# 74LV2G07DBVR.net
KiCad netlist of a schematic drawn in EAGLE
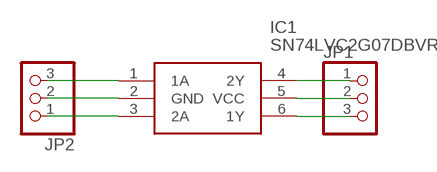
[diagram p0: schematic, sheet 1]

(export (version "E")
  (design (tool "Eeschema 10.0.6"))
  (components
    (comp (ref "IC1")
      (value "SN74LVC2G07DBVR")
      (footprint "eagle-import:SOT95P280X145-6N")
      (fields (field (name "RS_PART_NUMBER") "6628913P"))
      (libsource (lib "eagle-import") (part "SN74LVC2G07DBVR"))
    )
    (comp (ref "JP1")
      (value "PINHD-1X3")
      (footprint "eagle-import:1X03")
      (libsource (lib "eagle-import") (part "PINHD-1X3"))
    )
    (comp (ref "JP2")
      (value "PINHD-1X3")
      (footprint "eagle-import:1X03")
      (libsource (lib "eagle-import") (part "PINHD-1X3"))
    )
  )
  (nets
    (net (code "1") (name "Net-(IC1-1A)") (class "Default")
      (node (ref "IC1") (pin "1") (pinfunction "1A_1") (pintype "bidirectional"))
      (node (ref "JP2") (pin "3") (pinfunction "3_3") (pintype "passive"))
    )
    (net (code "2") (name "Net-(IC1-1Y)") (class "Default")
      (node (ref "IC1") (pin "6") (pinfunction "1Y_6") (pintype "bidirectional"))
      (node (ref "JP1") (pin "3") (pinfunction "3_3") (pintype "passive"))
    )
    (net (code "3") (name "Net-(IC1-2A)") (class "Default")
      (node (ref "IC1") (pin "3") (pinfunction "2A_3") (pintype "bidirectional"))
      (node (ref "JP2") (pin "1") (pinfunction "1_1") (pintype "passive"))
    )
    (net (code "4") (name "Net-(IC1-2Y)") (class "Default")
      (node (ref "IC1") (pin "4") (pinfunction "2Y_4") (pintype "bidirectional"))
      (node (ref "JP1") (pin "1") (pinfunction "1_1") (pintype "passive"))
    )
    (net (code "5") (name "Net-(IC1-GND)") (class "Default")
      (node (ref "IC1") (pin "2") (pinfunction "GND_2") (pintype "bidirectional"))
      (node (ref "JP2") (pin "2") (pinfunction "2_2") (pintype "passive"))
    )
    (net (code "6") (name "Net-(IC1-VCC)") (class "Default")
      (node (ref "IC1") (pin "5") (pinfunction "VCC_5") (pintype "bidirectional"))
      (node (ref "JP1") (pin "2") (pinfunction "2_2") (pintype "passive"))
    )
  )
)
